# fet_overdrive_v20.net
KiCad netlist of a schematic drawn in EAGLE
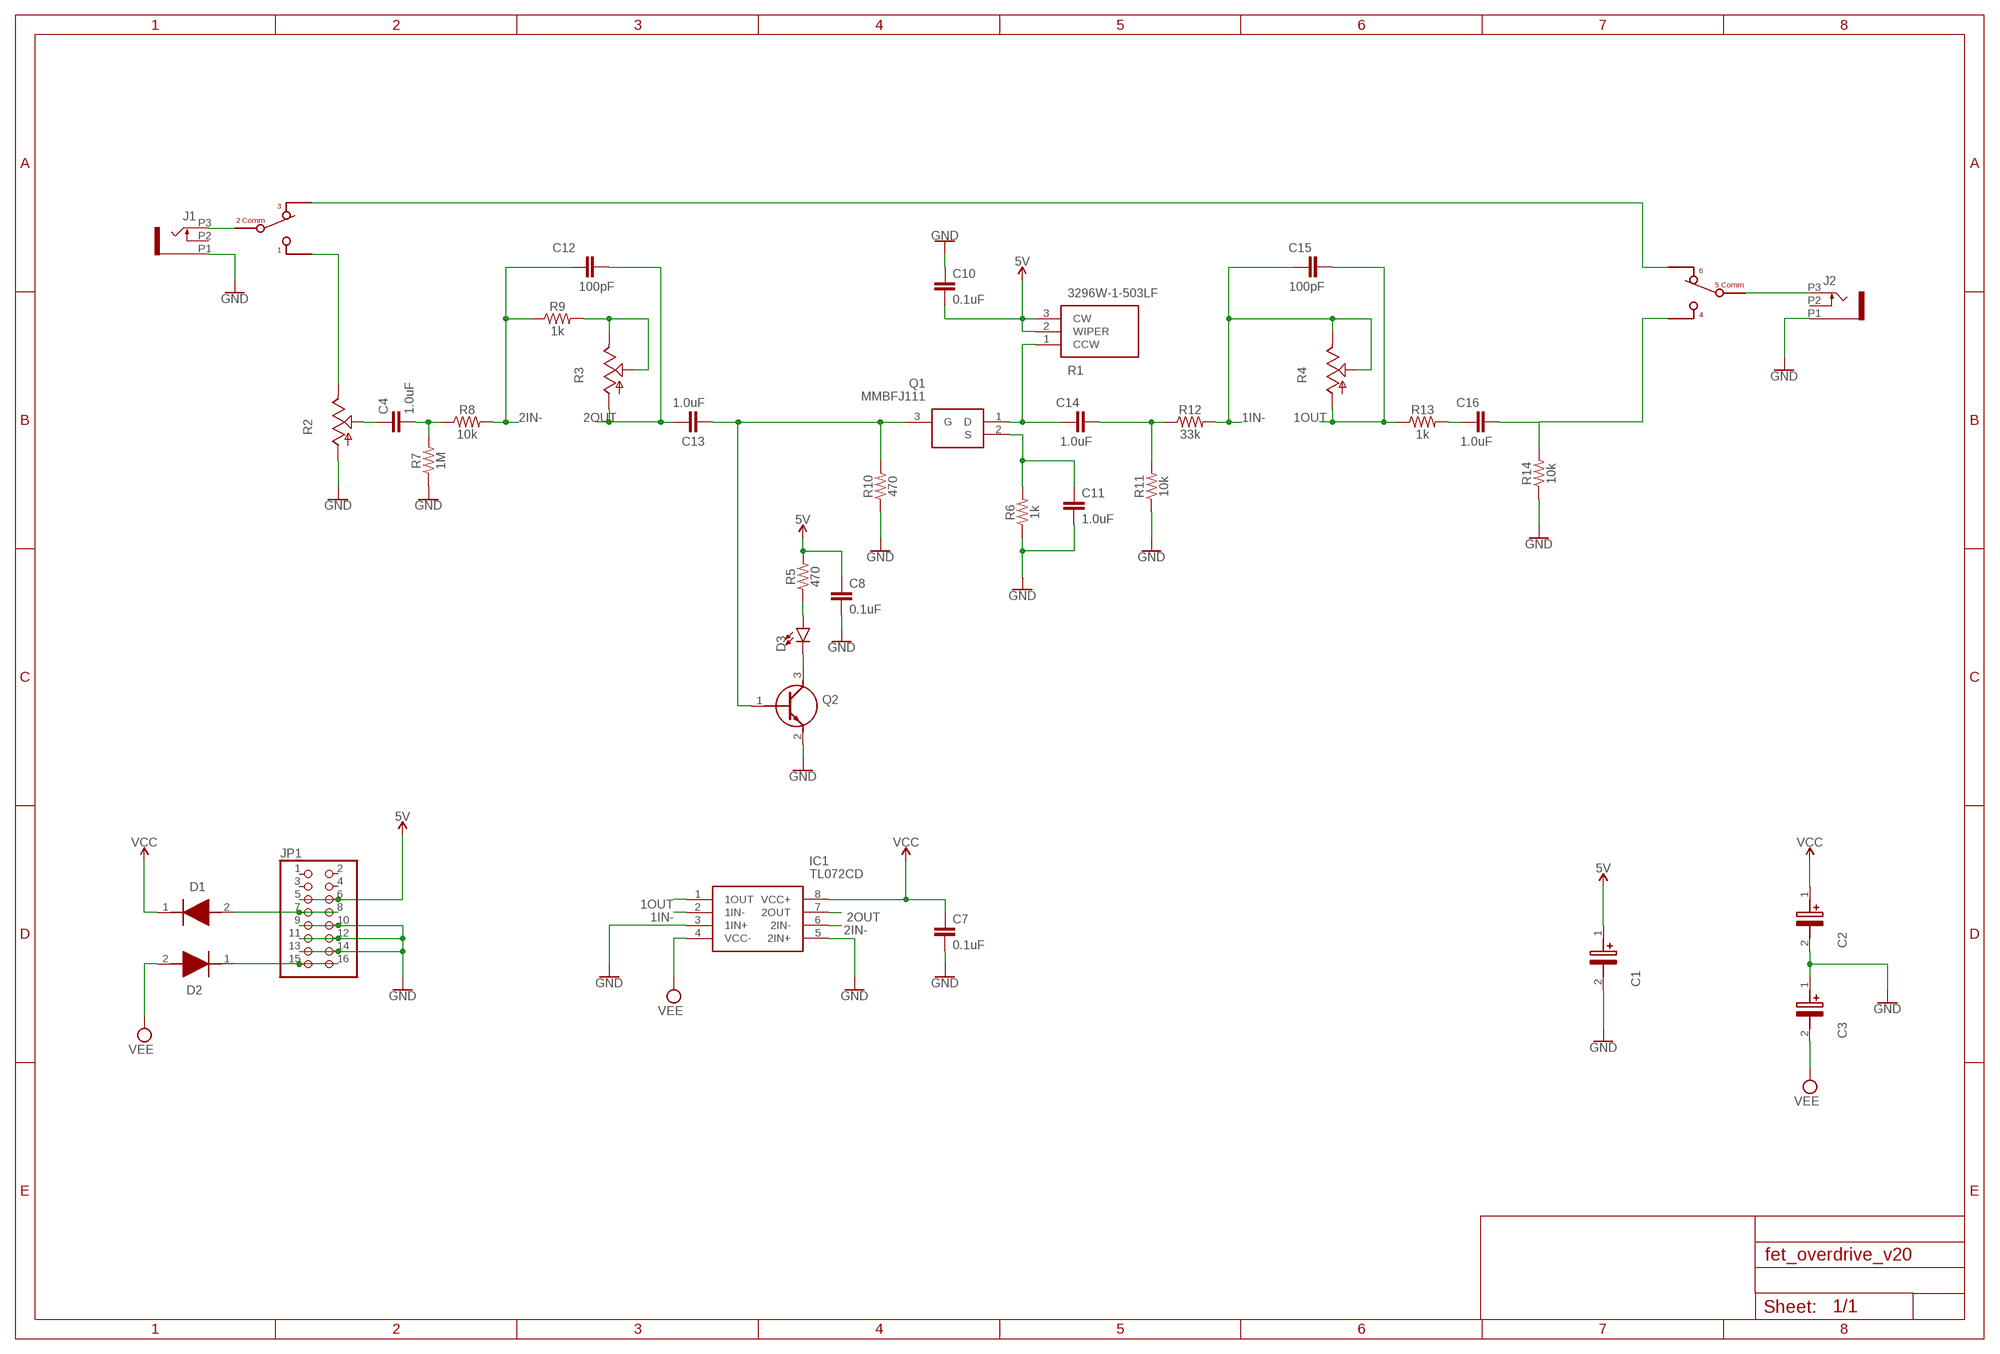
[diagram p0: schematic, sheet 1]

(export (version "E")
  (design (tool "Eeschema 10.0.6"))
  (components
    (comp (ref "C1")
      (value "EEE-FP1E220AR")
      (footprint "eagle-import:EEE0GA101SR")
      (fields (field (name "MOUSER_PART_NUMBER") "667-EEE-FP1E220AR"))
      (libsource (lib "eagle-import") (part "EEE-FP1E220AR"))
    )
    (comp (ref "C2")
      (value "EEE-FK1V470P")
      (footprint "eagle-import:EEE1AA101SP")
      (fields (field (name "MOUSER_PART_NUMBER") "667-EEE-FK1V470P"))
      (libsource (lib "eagle-import") (part "EEE-FK1V470P"))
    )
    (comp (ref "C3")
      (value "EEE-FK1V470P")
      (footprint "eagle-import:EEE1AA101SP")
      (fields (field (name "MOUSER_PART_NUMBER") "667-EEE-FK1V470P"))
      (libsource (lib "eagle-import") (part "EEE-FK1V470P"))
    )
    (comp (ref "C4")
      (value "1.0uF")
      (footprint "eagle-import:0603")
      (libsource (lib "eagle-import") (part "1.0UF-0603-16V-10%"))
    )
    (comp (ref "C7")
      (value "0.1uF")
      (footprint "eagle-import:0603")
      (libsource (lib "eagle-import") (part "0.1UF-0603-25V-5%"))
    )
    (comp (ref "C8")
      (value "0.1uF")
      (footprint "eagle-import:0603")
      (libsource (lib "eagle-import") (part "0.1UF-0603-25V-5%"))
    )
    (comp (ref "C10")
      (value "0.1uF")
      (footprint "eagle-import:0603")
      (libsource (lib "eagle-import") (part "0.1UF-0603-25V-5%"))
    )
    (comp (ref "C11")
      (value "1.0uF")
      (footprint "eagle-import:0603")
      (libsource (lib "eagle-import") (part "1.0UF-0603-16V-10%"))
    )
    (comp (ref "C12")
      (value "100pF")
      (footprint "eagle-import:0603")
      (libsource (lib "eagle-import") (part "100PF-0603-50V-5%"))
    )
    (comp (ref "C13")
      (value "1.0uF")
      (footprint "eagle-import:0603")
      (libsource (lib "eagle-import") (part "1.0UF-0603-16V-10%"))
    )
    (comp (ref "C14")
      (value "1.0uF")
      (footprint "eagle-import:0603")
      (libsource (lib "eagle-import") (part "1.0UF-0603-16V-10%"))
    )
    (comp (ref "C15")
      (value "100pF")
      (footprint "eagle-import:0603")
      (libsource (lib "eagle-import") (part "100PF-0603-50V-5%"))
    )
    (comp (ref "C16")
      (value "1.0uF")
      (footprint "eagle-import:0603")
      (libsource (lib "eagle-import") (part "1.0UF-0603-16V-10%"))
    )
    (comp (ref "D1")
      (value "1N5819HW-7-F")
      (footprint "eagle-import:SOD3716X145N")
      (fields (field (name "MOUSER_PART_NUMBER") "621-1N5819HW-F"))
      (libsource (lib "eagle-import") (part "1N5819HW-7-F"))
    )
    (comp (ref "D2")
      (value "1N5819HW-7-F")
      (footprint "eagle-import:SOD3716X145N")
      (fields (field (name "MOUSER_PART_NUMBER") "621-1N5819HW-F"))
      (libsource (lib "eagle-import") (part "1N5819HW-7-F"))
    )
    (comp (ref "D3")
      (value "LED3MM")
      (footprint "eagle-import:LED_3MM")
      (libsource (lib "eagle-import") (part "LED3MM"))
    )
    (comp (ref "IC1")
      (value "TL072CD")
      (footprint "eagle-import:SOIC127P600X175-8N")
      (fields (field (name "MOUSER_PART_NUMBER") "595-TL072CD"))
      (libsource (lib "eagle-import") (part "TL072CD"))
    )
    (comp (ref "J1")
      (value "PJ301_THONKICONN6")
      (footprint "eagle-import:WQP_PJ_301M6")
      (libsource (lib "eagle-import") (part "PJ301_THONKICONN6"))
    )
    (comp (ref "J2")
      (value "PJ301_THONKICONN6")
      (footprint "eagle-import:WQP_PJ_301M6")
      (libsource (lib "eagle-import") (part "PJ301_THONKICONN6"))
    )
    (comp (ref "JP1")
      (value "PINHD-2X8")
      (footprint "eagle-import:2X08")
      (libsource (lib "eagle-import") (part "PINHD-2X8"))
    )
    (comp (ref "Q1")
      (value "MMBFJ111")
      (footprint "eagle-import:SOT96P237X111-3N")
      (fields (field (name "MOUSER_PART_NUMBER") "512-MMBFJ111"))
      (libsource (lib "eagle-import") (part "MMBFJ111"))
    )
    (comp (ref "Q2")
      (value "SMMBT3904LT1G")
      (footprint "eagle-import:SOT96P237X111-3N")
      (fields (field (name "MOUSER_PART_NUMBER") "863-SMMBT3904LT1G"))
      (libsource (lib "eagle-import") (part "SMMBT3904LT1G"))
    )
    (comp (ref "R1")
      (value "3296W-1-503LF")
      (footprint "eagle-import:3296W-1")
      (fields (field (name "MOUSER_PART_NUMBER") "652-3296W-1-503LF"))
      (libsource (lib "eagle-import") (part "3296W-1-503LF"))
    )
    (comp (ref "R2")
      (value "POT_USVERTICAL_PS")
      (footprint "eagle-import:ALPS_POT_VERTICAL_PS")
      (libsource (lib "eagle-import") (part "POT_USVERTICAL_PS"))
    )
    (comp (ref "R3")
      (value "POT_USVERTICAL_PS")
      (footprint "eagle-import:ALPS_POT_VERTICAL_PS")
      (libsource (lib "eagle-import") (part "POT_USVERTICAL_PS"))
    )
    (comp (ref "R4")
      (value "POT_USVERTICAL_PS")
      (footprint "eagle-import:ALPS_POT_VERTICAL_PS")
      (libsource (lib "eagle-import") (part "POT_USVERTICAL_PS"))
    )
    (comp (ref "R5")
      (value "470")
      (footprint "eagle-import:0603")
      (libsource (lib "eagle-import") (part "470OHM-0603-1/10W-1%"))
    )
    (comp (ref "R6")
      (value "1k")
      (footprint "eagle-import:0603")
      (libsource (lib "eagle-import") (part "1KOHM-0603-1/10W-1%"))
    )
    (comp (ref "R7")
      (value "1M")
      (footprint "eagle-import:0603")
      (libsource (lib "eagle-import") (part "1MOHM-0603-1/4W-5%"))
    )
    (comp (ref "R8")
      (value "10k")
      (footprint "eagle-import:0603")
      (libsource (lib "eagle-import") (part "10KOHM-0603-1/10W-1%"))
    )
    (comp (ref "R9")
      (value "1k")
      (footprint "eagle-import:0603")
      (libsource (lib "eagle-import") (part "1KOHM-0603-1/10W-1%"))
    )
    (comp (ref "R10")
      (value "470")
      (footprint "eagle-import:0603")
      (libsource (lib "eagle-import") (part "470OHM-0603-1/10W-1%"))
    )
    (comp (ref "R11")
      (value "10k")
      (footprint "eagle-import:0603")
      (libsource (lib "eagle-import") (part "10KOHM-0603-1/10W-1%"))
    )
    (comp (ref "R12")
      (value "33k")
      (footprint "eagle-import:0603")
      (libsource (lib "eagle-import") (part "33KOHM-0603-1/10W-1%"))
    )
    (comp (ref "R13")
      (value "1k")
      (footprint "eagle-import:0603")
      (libsource (lib "eagle-import") (part "1KOHM-0603-1/10W-1%"))
    )
    (comp (ref "R14")
      (value "10k")
      (footprint "eagle-import:0603")
      (libsource (lib "eagle-import") (part "10KOHM-0603-1/10W-1%"))
    )
    (comp (ref "U$1")
      (value "DAILYWELL-DPDT")
      (footprint "eagle-import:DAILYWELL-DPDT")
      (libsource (lib "eagle-import") (part "DAILYWELL-DPDT"))
    )
  )
  (nets
    (net (code "1") (name "/1IN-") (class "Default")
      (node (ref "C15") (pin "1") (pinfunction "1_1") (pintype "passive"))
      (node (ref "IC1") (pin "2") (pinfunction "1IN-_2") (pintype "bidirectional"))
      (node (ref "R12") (pin "2") (pinfunction "2_2") (pintype "passive"))
      (node (ref "R4") (pin "P$1") (pinfunction "E_P$1") (pintype "passive"))
      (node (ref "R4") (pin "P$2") (pinfunction "S_P$2") (pintype "passive"))
    )
    (net (code "2") (name "/1OUT") (class "Default")
      (node (ref "C15") (pin "2") (pinfunction "2_2") (pintype "passive"))
      (node (ref "IC1") (pin "1") (pinfunction "1OUT_1") (pintype "bidirectional"))
      (node (ref "R13") (pin "1") (pinfunction "1_1") (pintype "passive"))
      (node (ref "R4") (pin "P$3") (pinfunction "A_P$3") (pintype "passive"))
    )
    (net (code "3") (name "/2IN-") (class "Default")
      (node (ref "C12") (pin "1") (pinfunction "1_1") (pintype "passive"))
      (node (ref "IC1") (pin "6") (pinfunction "2IN-_6") (pintype "bidirectional"))
      (node (ref "R8") (pin "2") (pinfunction "2_2") (pintype "passive"))
      (node (ref "R9") (pin "1") (pinfunction "1_1") (pintype "passive"))
    )
    (net (code "4") (name "/2OUT") (class "Default")
      (node (ref "C12") (pin "2") (pinfunction "2_2") (pintype "passive"))
      (node (ref "C13") (pin "1") (pinfunction "1_1") (pintype "passive"))
      (node (ref "IC1") (pin "7") (pinfunction "2OUT_7") (pintype "bidirectional"))
      (node (ref "R3") (pin "P$3") (pinfunction "A_P$3") (pintype "passive"))
    )
    (net (code "5") (name "5V") (class "Default")
      (node (ref "C1") (pin "1") (pinfunction "+_1") (pintype "bidirectional"))
      (node (ref "C10") (pin "2") (pinfunction "2_2") (pintype "passive"))
      (node (ref "C8") (pin "1") (pinfunction "1_1") (pintype "passive"))
      (node (ref "JP1") (pin "5") (pinfunction "5_5") (pintype "passive"))
      (node (ref "JP1") (pin "6") (pinfunction "6_6") (pintype "passive"))
      (node (ref "R1") (pin "2") (pinfunction "WIPER_2") (pintype "bidirectional"))
      (node (ref "R1") (pin "3") (pinfunction "CW_3") (pintype "bidirectional"))
      (node (ref "R5") (pin "2") (pinfunction "2_2") (pintype "passive"))
    )
    (net (code "6") (name "GND") (class "Default")
      (node (ref "C1") (pin "2") (pinfunction "-_2") (pintype "bidirectional"))
      (node (ref "C10") (pin "1") (pinfunction "1_1") (pintype "passive"))
      (node (ref "C11") (pin "2") (pinfunction "2_2") (pintype "passive"))
      (node (ref "C2") (pin "2") (pinfunction "-_2") (pintype "bidirectional"))
      (node (ref "C3") (pin "1") (pinfunction "+_1") (pintype "bidirectional"))
      (node (ref "C7") (pin "2") (pinfunction "2_2") (pintype "passive"))
      (node (ref "C8") (pin "2") (pinfunction "2_2") (pintype "passive"))
      (node (ref "IC1") (pin "3") (pinfunction "1IN+_3") (pintype "bidirectional"))
      (node (ref "IC1") (pin "5") (pinfunction "2IN+_5") (pintype "bidirectional"))
      (node (ref "J1") (pin "P1") (pinfunction "1_P1") (pintype "passive"))
      (node (ref "J2") (pin "P1") (pinfunction "1_P1") (pintype "passive"))
      (node (ref "JP1") (pin "10") (pinfunction "10_10") (pintype "passive"))
      (node (ref "JP1") (pin "11") (pinfunction "11_11") (pintype "passive"))
      (node (ref "JP1") (pin "12") (pinfunction "12_12") (pintype "passive"))
      (node (ref "JP1") (pin "13") (pinfunction "13_13") (pintype "passive"))
      (node (ref "JP1") (pin "14") (pinfunction "14_14") (pintype "passive"))
      (node (ref "JP1") (pin "9") (pinfunction "9_9") (pintype "passive"))
      (node (ref "Q2") (pin "2") (pinfunction "E_2") (pintype "bidirectional"))
      (node (ref "R10") (pin "1") (pinfunction "1_1") (pintype "passive"))
      (node (ref "R11") (pin "1") (pinfunction "1_1") (pintype "passive"))
      (node (ref "R14") (pin "1") (pinfunction "1_1") (pintype "passive"))
      (node (ref "R2") (pin "P$3") (pinfunction "A_P$3") (pintype "passive"))
      (node (ref "R6") (pin "1") (pinfunction "1_1") (pintype "passive"))
      (node (ref "R7") (pin "1") (pinfunction "1_1") (pintype "passive"))
    )
    (net (code "7") (name "Net-(C4-Pad2)") (class "Default")
      (node (ref "C4") (pin "2") (pinfunction "2_2") (pintype "passive"))
      (node (ref "R7") (pin "2") (pinfunction "2_2") (pintype "passive"))
      (node (ref "R8") (pin "1") (pinfunction "1_1") (pintype "passive"))
    )
    (net (code "8") (name "Net-(C14-Pad2)") (class "Default")
      (node (ref "C14") (pin "2") (pinfunction "2_2") (pintype "passive"))
      (node (ref "R11") (pin "2") (pinfunction "2_2") (pintype "passive"))
      (node (ref "R12") (pin "1") (pinfunction "1_1") (pintype "passive"))
    )
    (net (code "9") (name "Net-(C16-Pad1)") (class "Default")
      (node (ref "C16") (pin "1") (pinfunction "1_1") (pintype "passive"))
      (node (ref "R13") (pin "2") (pinfunction "2_2") (pintype "passive"))
    )
    (net (code "10") (name "Net-(D1-A)") (class "Default")
      (node (ref "D1") (pin "2") (pinfunction "A_2") (pintype "bidirectional"))
      (node (ref "JP1") (pin "7") (pinfunction "7_7") (pintype "passive"))
      (node (ref "JP1") (pin "8") (pinfunction "8_8") (pintype "passive"))
    )
    (net (code "11") (name "Net-(D2-K)") (class "Default")
      (node (ref "D2") (pin "1") (pinfunction "K_1") (pintype "bidirectional"))
      (node (ref "JP1") (pin "15") (pinfunction "15_15") (pintype "passive"))
      (node (ref "JP1") (pin "16") (pinfunction "16_16") (pintype "passive"))
    )
    (net (code "12") (name "Net-(D3-C)") (class "Default")
      (node (ref "D3") (pin "K") (pinfunction "C_K") (pintype "passive"))
      (node (ref "Q2") (pin "3") (pinfunction "C_3") (pintype "bidirectional"))
    )
    (net (code "13") (name "Net-(D3-PadA)") (class "Default")
      (node (ref "D3") (pin "A") (pinfunction "A_A") (pintype "passive"))
      (node (ref "R5") (pin "1") (pinfunction "1_1") (pintype "passive"))
    )
    (net (code "14") (name "Net-(J1-3)") (class "Default")
      (node (ref "J1") (pin "P3") (pinfunction "3_P3") (pintype "passive"))
      (node (ref "U$1") (pin "P$2") (pinfunction "P$2_P$2") (pintype "bidirectional"))
    )
    (net (code "15") (name "Net-(J2-3)") (class "Default")
      (node (ref "J2") (pin "P3") (pinfunction "3_P3") (pintype "passive"))
      (node (ref "U$1") (pin "P$5") (pinfunction "P$2_P$5") (pintype "bidirectional"))
    )
    (net (code "16") (name "Net-(Q1-D)") (class "Default")
      (node (ref "C14") (pin "1") (pinfunction "1_1") (pintype "passive"))
      (node (ref "Q1") (pin "1") (pinfunction "D_1") (pintype "bidirectional"))
      (node (ref "R1") (pin "1") (pinfunction "CCW_1") (pintype "bidirectional"))
    )
    (net (code "17") (name "Net-(Q1-G)") (class "Default")
      (node (ref "C13") (pin "2") (pinfunction "2_2") (pintype "passive"))
      (node (ref "Q1") (pin "3") (pinfunction "G_3") (pintype "bidirectional"))
      (node (ref "Q2") (pin "1") (pinfunction "B_1") (pintype "bidirectional"))
      (node (ref "R10") (pin "2") (pinfunction "2_2") (pintype "passive"))
    )
    (net (code "18") (name "Net-(Q1-S)") (class "Default")
      (node (ref "C11") (pin "1") (pinfunction "1_1") (pintype "passive"))
      (node (ref "Q1") (pin "2") (pinfunction "S_2") (pintype "bidirectional"))
      (node (ref "R6") (pin "2") (pinfunction "2_2") (pintype "passive"))
    )
    (net (code "19") (name "Net-(R2-E)") (class "Default")
      (node (ref "R2") (pin "P$1") (pinfunction "E_P$1") (pintype "passive"))
      (node (ref "U$1") (pin "P$1") (pinfunction "P$1_P$1") (pintype "bidirectional"))
    )
    (net (code "20") (name "Net-(R2-S)") (class "Default")
      (node (ref "C4") (pin "1") (pinfunction "1_1") (pintype "passive"))
      (node (ref "R2") (pin "P$2") (pinfunction "S_P$2") (pintype "passive"))
    )
    (net (code "21") (name "Net-(R3-E)") (class "Default")
      (node (ref "R3") (pin "P$1") (pinfunction "E_P$1") (pintype "passive"))
      (node (ref "R3") (pin "P$2") (pinfunction "S_P$2") (pintype "passive"))
      (node (ref "R9") (pin "2") (pinfunction "2_2") (pintype "passive"))
    )
    (net (code "22") (name "Net-(U$1B-P$1)") (class "Default")
      (node (ref "C16") (pin "2") (pinfunction "2_2") (pintype "passive"))
      (node (ref "R14") (pin "2") (pinfunction "2_2") (pintype "passive"))
      (node (ref "U$1") (pin "P$4") (pinfunction "P$1_P$4") (pintype "bidirectional"))
    )
    (net (code "23") (name "Net-(U$1B-P$3)") (class "Default")
      (node (ref "U$1") (pin "P$3") (pinfunction "P$3_P$3") (pintype "bidirectional"))
      (node (ref "U$1") (pin "P$6") (pinfunction "P$3_P$6") (pintype "bidirectional"))
    )
    (net (code "24") (name "VCC") (class "Default")
      (node (ref "C2") (pin "1") (pinfunction "+_1") (pintype "bidirectional"))
      (node (ref "C7") (pin "1") (pinfunction "1_1") (pintype "passive"))
      (node (ref "D1") (pin "1") (pinfunction "K_1") (pintype "bidirectional"))
      (node (ref "IC1") (pin "8") (pinfunction "VCC+_8") (pintype "bidirectional"))
    )
    (net (code "25") (name "VEE") (class "Default")
      (node (ref "C3") (pin "2") (pinfunction "-_2") (pintype "bidirectional"))
      (node (ref "D2") (pin "2") (pinfunction "A_2") (pintype "bidirectional"))
      (node (ref "IC1") (pin "4") (pinfunction "VCC-_4") (pintype "bidirectional"))
    )
    (net (code "26") (name "unconnected-(J1-2-PadP2)") (class "Default")
      (node (ref "J1") (pin "P2") (pinfunction "2_P2") (pintype "passive"))
    )
    (net (code "27") (name "unconnected-(J2-2-PadP2)") (class "Default")
      (node (ref "J2") (pin "P2") (pinfunction "2_P2") (pintype "passive"))
    )
    (net (code "28") (name "unconnected-(JP1-Pad1)") (class "Default")
      (node (ref "JP1") (pin "1") (pinfunction "1_1") (pintype "passive"))
    )
    (net (code "29") (name "unconnected-(JP1-Pad2)") (class "Default")
      (node (ref "JP1") (pin "2") (pinfunction "2_2") (pintype "passive"))
    )
    (net (code "30") (name "unconnected-(JP1-Pad3)") (class "Default")
      (node (ref "JP1") (pin "3") (pinfunction "3_3") (pintype "passive"))
    )
    (net (code "31") (name "unconnected-(JP1-Pad4)") (class "Default")
      (node (ref "JP1") (pin "4") (pinfunction "4_4") (pintype "passive"))
    )
  )
)
